# Solenoid_4.net
KiCad netlist of a schematic drawn in EAGLE
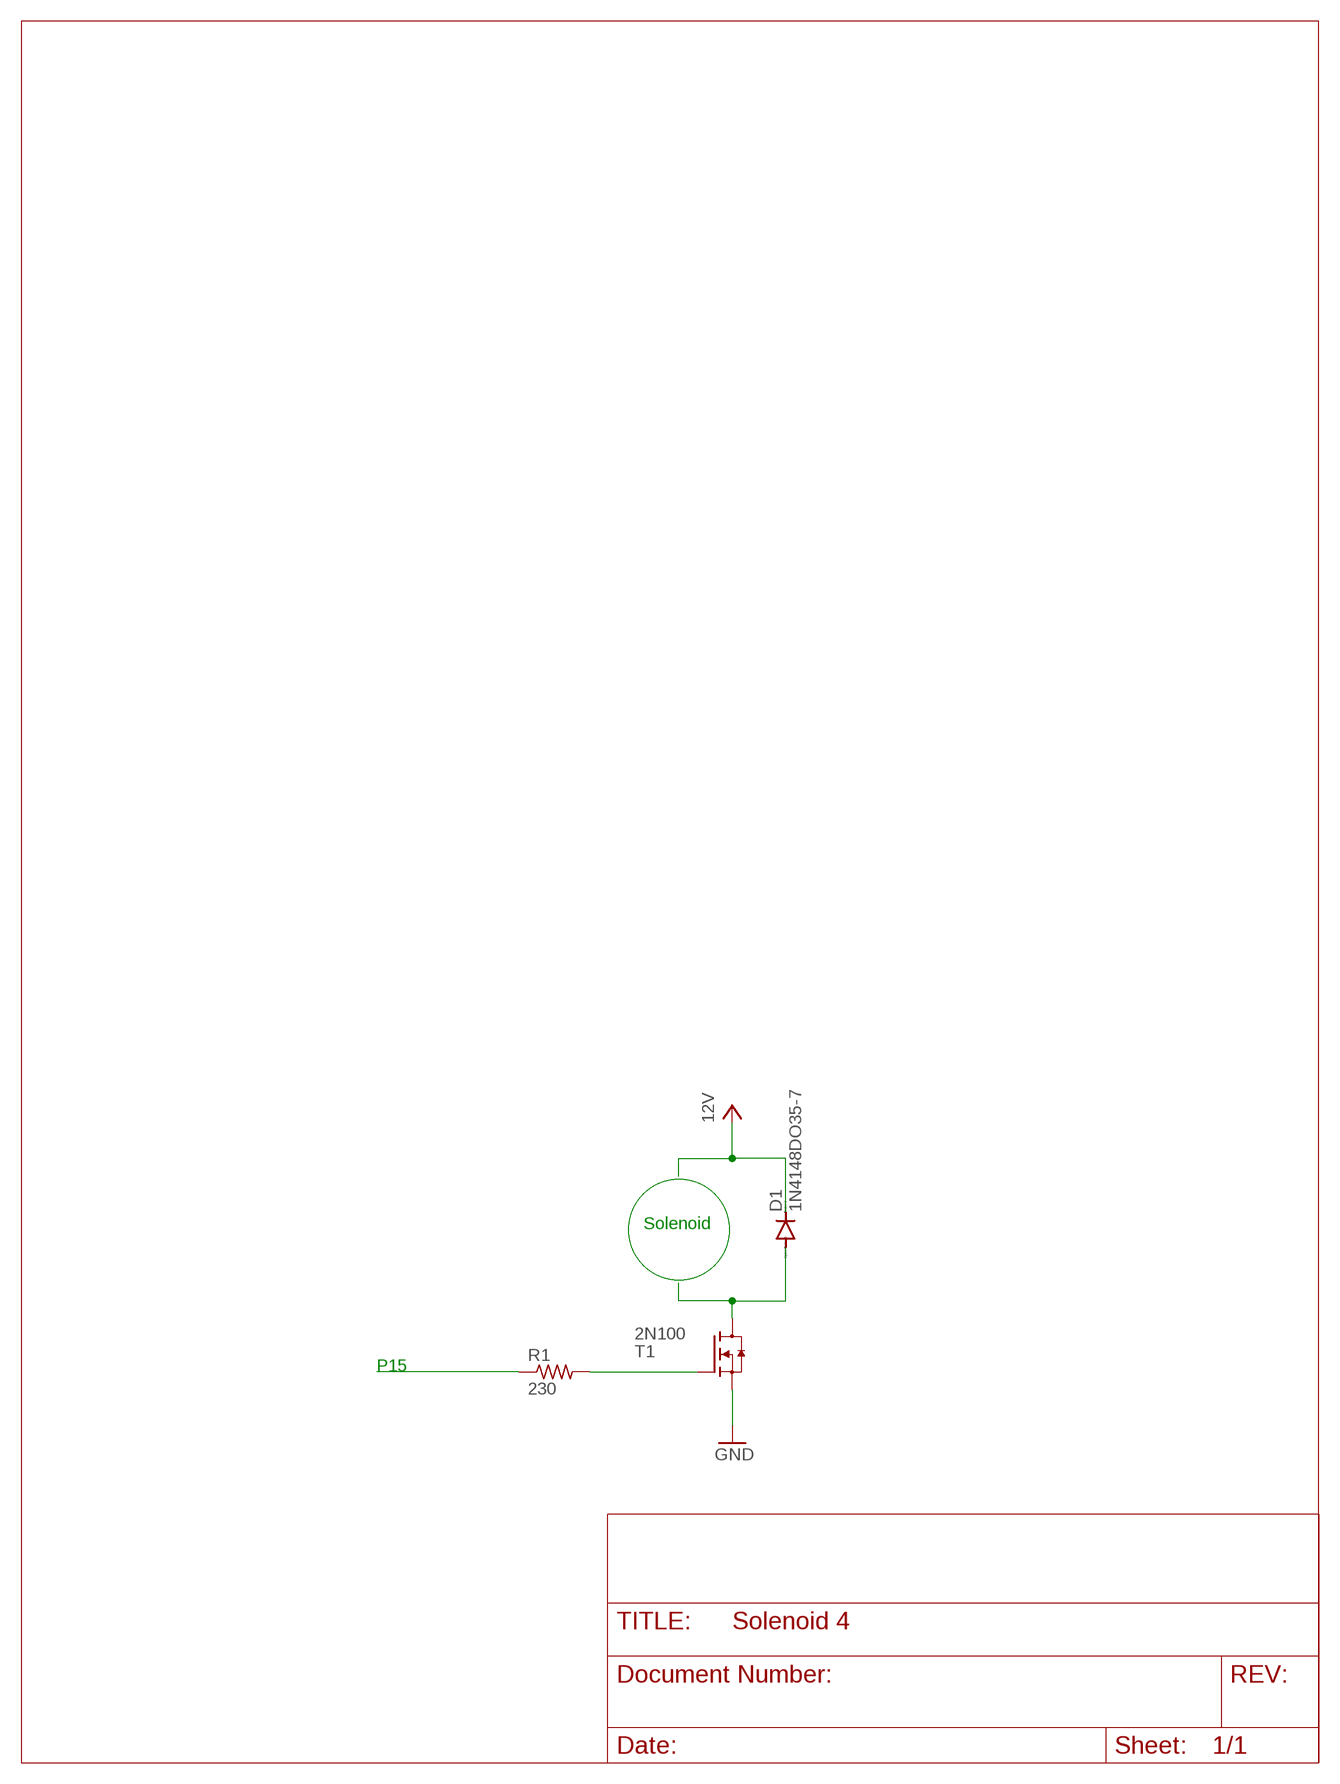
[diagram p0: schematic, sheet 1]

(export (version "E")
  (design (tool "Eeschema 10.0.6"))
  (components
    (comp (ref "D1")
      (value "1N4148DO35-7")
      (footprint "eagle-import:DO35-7")
      (libsource (lib "eagle-import") (part "1N4148DO35-7"))
    )
    (comp (ref "R1")
      (value "230")
      (footprint "eagle-import:0204_7")
      (libsource (lib "eagle-import") (part "R-US_0204/7"))
    )
    (comp (ref "T1")
      (value "2N100")
      (footprint "eagle-import:PG-TO263-7-3")
      (libsource (lib "eagle-import") (part "IPB180N06S4-H1"))
    )
  )
  (nets
    (net (code "1") (name "12V") (class "Default")
      (node (ref "D1") (pin "C") (pinfunction "C_C") (pintype "passive"))
    )
    (net (code "2") (name "GND") (class "Default")
      (node (ref "T1") (pin "2") (pinfunction "S_2") (pintype "passive"))
      (node (ref "T1") (pin "3") (pinfunction "S_3") (pintype "passive"))
      (node (ref "T1") (pin "5") (pinfunction "S_5") (pintype "passive"))
      (node (ref "T1") (pin "6") (pinfunction "S_6") (pintype "passive"))
      (node (ref "T1") (pin "7") (pinfunction "S_7") (pintype "passive"))
    )
    (net (code "3") (name "Net-(T1-D)") (class "Default")
      (node (ref "D1") (pin "A") (pinfunction "A_A") (pintype "passive"))
      (node (ref "T1") (pin "8") (pinfunction "D_8") (pintype "passive"))
    )
    (net (code "4") (name "Net-(T1-G)") (class "Default")
      (node (ref "R1") (pin "2") (pinfunction "2_2") (pintype "passive"))
      (node (ref "T1") (pin "1") (pinfunction "G_1") (pintype "passive"))
    )
    (net (code "5") (name "unconnected-(R1-Pad1)") (class "Default")
      (node (ref "R1") (pin "1") (pinfunction "1_1") (pintype "passive"))
    )
  )
)
